# Connections.net
KiCad netlist of a schematic drawn in EAGLE
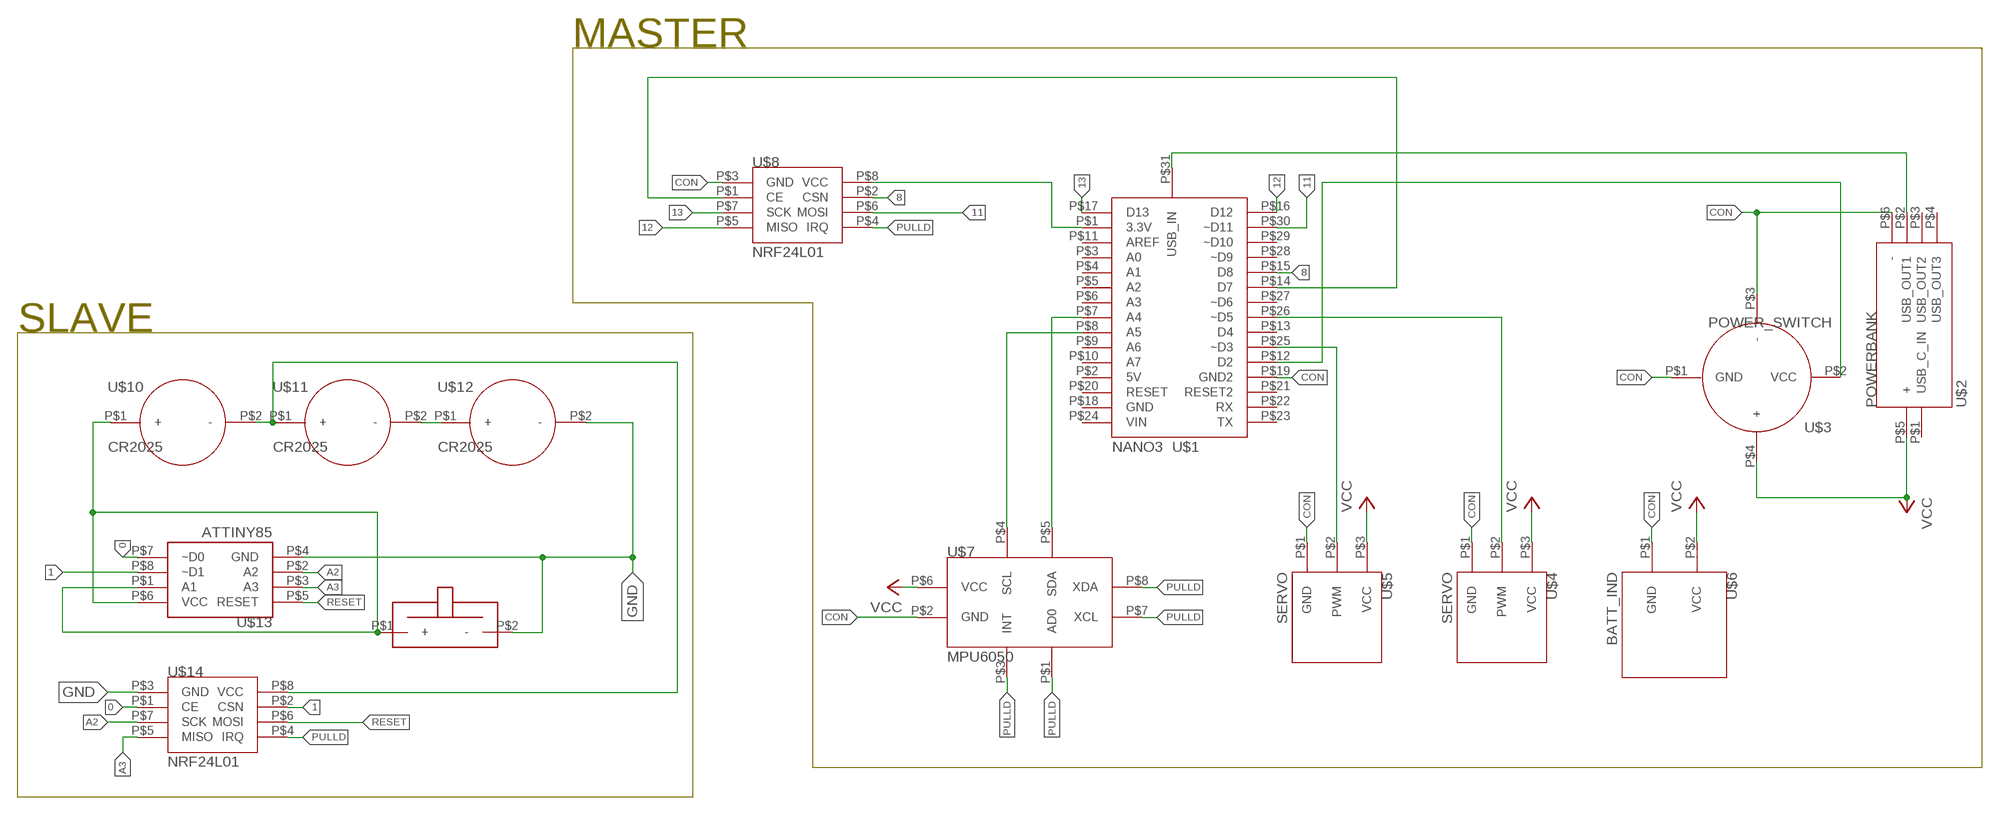
[diagram p0: schematic, sheet 1]

(export (version "E")
  (design (tool "Eeschema 10.0.6"))
  (components
    (comp (ref "U$1")
      (value "NANO3")
      (footprint "eagle-import:NANO3")
      (libsource (lib "eagle-import") (part "NANO3"))
    )
    (comp (ref "U$2")
      (value "POWERBANK")
      (footprint "eagle-import:POWERBANK")
      (libsource (lib "eagle-import") (part "POWERBANK"))
    )
    (comp (ref "U$3")
      (value "POWER_SWITCH")
      (footprint "eagle-import:POWER_SWITCH")
      (libsource (lib "eagle-import") (part "POWER_SWITCH"))
    )
    (comp (ref "U$4")
      (value "SERVO")
      (footprint "eagle-import:SERVO")
      (libsource (lib "eagle-import") (part "SERVO"))
    )
    (comp (ref "U$5")
      (value "SERVO")
      (footprint "eagle-import:SERVO")
      (libsource (lib "eagle-import") (part "SERVO"))
    )
    (comp (ref "U$6")
      (value "BATT_IND")
      (footprint "eagle-import:BATT_IND")
      (libsource (lib "eagle-import") (part "BATT_IND"))
    )
    (comp (ref "U$7")
      (value "MPU6050")
      (footprint "eagle-import:MPU6050")
      (libsource (lib "eagle-import") (part "MPU6050"))
    )
    (comp (ref "U$8")
      (value "NRF24L01")
      (footprint "eagle-import:NRF24L01")
      (libsource (lib "eagle-import") (part "NRF24L01"))
    )
    (comp (ref "U$9")
      (value "SPST")
      (footprint "eagle-import:SPST")
      (libsource (lib "eagle-import") (part "SPST"))
    )
    (comp (ref "U$10")
      (value "CR2025")
      (footprint "eagle-import:CR2025")
      (libsource (lib "eagle-import") (part "CR2025"))
    )
    (comp (ref "U$11")
      (value "CR2025")
      (footprint "eagle-import:CR2025")
      (libsource (lib "eagle-import") (part "CR2025"))
    )
    (comp (ref "U$12")
      (value "CR2025")
      (footprint "eagle-import:CR2025")
      (libsource (lib "eagle-import") (part "CR2025"))
    )
    (comp (ref "U$13")
      (value "ATTINY85")
      (footprint "eagle-import:ATTINY85")
      (libsource (lib "eagle-import") (part "ATTINY85"))
    )
    (comp (ref "U$14")
      (value "NRF24L01")
      (footprint "eagle-import:NRF24L01")
      (libsource (lib "eagle-import") (part "NRF24L01"))
    )
  )
  (nets
    (net (code "1") (name "0") (class "Default")
      (node (ref "U$13") (pin "P$7") (pinfunction "~{D0}_P$7") (pintype "bidirectional"))
    )
    (net (code "2") (name "1") (class "Default")
      (node (ref "U$13") (pin "P$8") (pinfunction "~{D1}_P$8") (pintype "bidirectional"))
    )
    (net (code "3") (name "8") (class "Default")
      (node (ref "U$1") (pin "P$15") (pinfunction "D8_P$15") (pintype "bidirectional"))
    )
    (net (code "4") (name "11") (class "Default")
      (node (ref "U$1") (pin "P$30") (pinfunction "~{D11}_P$30") (pintype "bidirectional"))
    )
    (net (code "5") (name "12") (class "Default")
      (node (ref "U$8") (pin "P$5") (pinfunction "MISO_P$5") (pintype "bidirectional"))
    )
    (net (code "6") (name "13") (class "Default")
      (node (ref "U$8") (pin "P$7") (pinfunction "SCK_P$7") (pintype "bidirectional"))
    )
    (net (code "7") (name "A2") (class "Default")
      (node (ref "U$13") (pin "P$2") (pinfunction "A2_P$2") (pintype "bidirectional"))
    )
    (net (code "8") (name "A3") (class "Default")
      (node (ref "U$13") (pin "P$3") (pinfunction "A3_P$3") (pintype "bidirectional"))
    )
    (net (code "9") (name "CON") (class "Default")
      (node (ref "U$1") (pin "P$19") (pinfunction "GND2_P$19") (pintype "bidirectional"))
    )
    (net (code "10") (name "GND") (class "Default")
      (node (ref "U$12") (pin "P$2") (pinfunction "-_P$2") (pintype "bidirectional"))
      (node (ref "U$13") (pin "P$4") (pinfunction "GND_P$4") (pintype "bidirectional"))
      (node (ref "U$9") (pin "P$2") (pinfunction "-_P$2") (pintype "bidirectional"))
    )
    (net (code "11") (name "Net-(U$1-3.3V)") (class "Default")
      (node (ref "U$1") (pin "P$1") (pinfunction "3.3V_P$1") (pintype "bidirectional"))
      (node (ref "U$8") (pin "P$8") (pinfunction "VCC_P$8") (pintype "bidirectional"))
    )
    (net (code "12") (name "Net-(U$1-A4)") (class "Default")
      (node (ref "U$1") (pin "P$7") (pinfunction "A4_P$7") (pintype "bidirectional"))
      (node (ref "U$7") (pin "P$5") (pinfunction "SDA_P$5") (pintype "bidirectional"))
    )
    (net (code "13") (name "Net-(U$1-A5)") (class "Default")
      (node (ref "U$1") (pin "P$8") (pinfunction "A5_P$8") (pintype "bidirectional"))
      (node (ref "U$7") (pin "P$4") (pinfunction "SCL_P$4") (pintype "bidirectional"))
    )
    (net (code "14") (name "Net-(U$1-D2)") (class "Default")
      (node (ref "U$1") (pin "P$12") (pinfunction "D2_P$12") (pintype "bidirectional"))
      (node (ref "U$3") (pin "P$2") (pinfunction "VCC_P$2") (pintype "bidirectional"))
    )
    (net (code "15") (name "Net-(U$1-D7)") (class "Default")
      (node (ref "U$1") (pin "P$14") (pinfunction "D7_P$14") (pintype "bidirectional"))
      (node (ref "U$8") (pin "P$1") (pinfunction "CE_P$1") (pintype "bidirectional"))
    )
    (net (code "16") (name "Net-(U$1-USB_IN)") (class "Default")
      (node (ref "U$1") (pin "P$31") (pinfunction "USB_IN_P$31") (pintype "bidirectional"))
      (node (ref "U$2") (pin "P$2") (pinfunction "USB_OUT1_P$2") (pintype "bidirectional"))
    )
    (net (code "17") (name "Net-(U$1-~{D3})") (class "Default")
      (node (ref "U$1") (pin "P$25") (pinfunction "~{D3}_P$25") (pintype "bidirectional"))
      (node (ref "U$5") (pin "P$2") (pinfunction "PWM_P$2") (pintype "bidirectional"))
    )
    (net (code "18") (name "Net-(U$1-~{D5})") (class "Default")
      (node (ref "U$1") (pin "P$26") (pinfunction "~{D5}_P$26") (pintype "bidirectional"))
      (node (ref "U$4") (pin "P$2") (pinfunction "PWM_P$2") (pintype "bidirectional"))
    )
    (net (code "19") (name "Net-(U$2--)") (class "Default")
      (node (ref "U$2") (pin "P$6") (pinfunction "-_P$6") (pintype "bidirectional"))
      (node (ref "U$3") (pin "P$3") (pinfunction "-_P$3") (pintype "bidirectional"))
    )
    (net (code "20") (name "Net-(U$10-+)") (class "Default")
      (node (ref "U$10") (pin "P$1") (pinfunction "+_P$1") (pintype "bidirectional"))
      (node (ref "U$13") (pin "P$1") (pinfunction "A1_P$1") (pintype "bidirectional"))
      (node (ref "U$13") (pin "P$6") (pinfunction "VCC_P$6") (pintype "bidirectional"))
      (node (ref "U$9") (pin "P$1") (pinfunction "+_P$1") (pintype "bidirectional"))
    )
    (net (code "21") (name "Net-(U$10--)") (class "Default")
      (node (ref "U$10") (pin "P$2") (pinfunction "-_P$2") (pintype "bidirectional"))
      (node (ref "U$11") (pin "P$1") (pinfunction "+_P$1") (pintype "bidirectional"))
      (node (ref "U$14") (pin "P$8") (pinfunction "VCC_P$8") (pintype "bidirectional"))
    )
    (net (code "22") (name "Net-(U$11--)") (class "Default")
      (node (ref "U$11") (pin "P$2") (pinfunction "-_P$2") (pintype "bidirectional"))
      (node (ref "U$12") (pin "P$1") (pinfunction "+_P$1") (pintype "bidirectional"))
    )
    (net (code "23") (name "PULLD") (class "Default")
      (node (ref "U$7") (pin "P$8") (pinfunction "XDA_P$8") (pintype "bidirectional"))
    )
    (net (code "24") (name "RESET") (class "Default")
      (node (ref "U$13") (pin "P$5") (pinfunction "RESET_P$5") (pintype "bidirectional"))
    )
    (net (code "25") (name "VCC") (class "Default")
      (node (ref "U$2") (pin "P$5") (pinfunction "+_P$5") (pintype "bidirectional"))
      (node (ref "U$3") (pin "P$4") (pinfunction "+_P$4") (pintype "bidirectional"))
      (node (ref "U$4") (pin "P$3") (pinfunction "VCC_P$3") (pintype "bidirectional"))
      (node (ref "U$5") (pin "P$3") (pinfunction "VCC_P$3") (pintype "bidirectional"))
      (node (ref "U$6") (pin "P$2") (pinfunction "VCC_P$2") (pintype "bidirectional"))
      (node (ref "U$7") (pin "P$6") (pinfunction "VCC_P$6") (pintype "bidirectional"))
    )
    (net (code "26") (name "unconnected-(U$1-5V-PadP$2)") (class "Default")
      (node (ref "U$1") (pin "P$2") (pinfunction "5V_P$2") (pintype "bidirectional"))
    )
    (net (code "27") (name "unconnected-(U$1-A0-PadP$3)") (class "Default")
      (node (ref "U$1") (pin "P$3") (pinfunction "A0_P$3") (pintype "bidirectional"))
    )
    (net (code "28") (name "unconnected-(U$1-A1-PadP$4)") (class "Default")
      (node (ref "U$1") (pin "P$4") (pinfunction "A1_P$4") (pintype "bidirectional"))
    )
    (net (code "29") (name "unconnected-(U$1-A2-PadP$5)") (class "Default")
      (node (ref "U$1") (pin "P$5") (pinfunction "A2_P$5") (pintype "bidirectional"))
    )
    (net (code "30") (name "unconnected-(U$1-A3-PadP$6)") (class "Default")
      (node (ref "U$1") (pin "P$6") (pinfunction "A3_P$6") (pintype "bidirectional"))
    )
    (net (code "31") (name "unconnected-(U$1-A6-PadP$9)") (class "Default")
      (node (ref "U$1") (pin "P$9") (pinfunction "A6_P$9") (pintype "bidirectional"))
    )
    (net (code "32") (name "unconnected-(U$1-A7-PadP$10)") (class "Default")
      (node (ref "U$1") (pin "P$10") (pinfunction "A7_P$10") (pintype "bidirectional"))
    )
    (net (code "33") (name "unconnected-(U$1-AREF-PadP$11)") (class "Default")
      (node (ref "U$1") (pin "P$11") (pinfunction "AREF_P$11") (pintype "bidirectional"))
    )
    (net (code "34") (name "unconnected-(U$1-D4-PadP$13)") (class "Default")
      (node (ref "U$1") (pin "P$13") (pinfunction "D4_P$13") (pintype "bidirectional"))
    )
    (net (code "35") (name "unconnected-(U$1-D12-PadP$16)") (class "Default")
      (node (ref "U$1") (pin "P$16") (pinfunction "D12_P$16") (pintype "bidirectional"))
    )
    (net (code "36") (name "unconnected-(U$1-D13-PadP$17)") (class "Default")
      (node (ref "U$1") (pin "P$17") (pinfunction "D13_P$17") (pintype "bidirectional"))
    )
    (net (code "37") (name "unconnected-(U$1-GND-PadP$18)") (class "Default")
      (node (ref "U$1") (pin "P$18") (pinfunction "GND_P$18") (pintype "bidirectional"))
    )
    (net (code "38") (name "unconnected-(U$1-RESET-PadP$20)") (class "Default")
      (node (ref "U$1") (pin "P$20") (pinfunction "RESET_P$20") (pintype "bidirectional"))
    )
    (net (code "39") (name "unconnected-(U$1-RESET2-PadP$21)") (class "Default")
      (node (ref "U$1") (pin "P$21") (pinfunction "RESET2_P$21") (pintype "bidirectional"))
    )
    (net (code "40") (name "unconnected-(U$1-RX-PadP$22)") (class "Default")
      (node (ref "U$1") (pin "P$22") (pinfunction "RX_P$22") (pintype "bidirectional"))
    )
    (net (code "41") (name "unconnected-(U$1-TX-PadP$23)") (class "Default")
      (node (ref "U$1") (pin "P$23") (pinfunction "TX_P$23") (pintype "bidirectional"))
    )
    (net (code "42") (name "unconnected-(U$1-VIN-PadP$24)") (class "Default")
      (node (ref "U$1") (pin "P$24") (pinfunction "VIN_P$24") (pintype "bidirectional"))
    )
    (net (code "43") (name "unconnected-(U$1-~{D6}-PadP$27)") (class "Default")
      (node (ref "U$1") (pin "P$27") (pinfunction "~{D6}_P$27") (pintype "bidirectional"))
    )
    (net (code "44") (name "unconnected-(U$1-~{D9}-PadP$28)") (class "Default")
      (node (ref "U$1") (pin "P$28") (pinfunction "~{D9}_P$28") (pintype "bidirectional"))
    )
    (net (code "45") (name "unconnected-(U$1-~{D10}-PadP$29)") (class "Default")
      (node (ref "U$1") (pin "P$29") (pinfunction "~{D10}_P$29") (pintype "bidirectional"))
    )
    (net (code "46") (name "unconnected-(U$2-USB_C_IN-PadP$1)") (class "Default")
      (node (ref "U$2") (pin "P$1") (pinfunction "USB_C_IN_P$1") (pintype "bidirectional"))
    )
    (net (code "47") (name "unconnected-(U$2-USB_OUT2-PadP$3)") (class "Default")
      (node (ref "U$2") (pin "P$3") (pinfunction "USB_OUT2_P$3") (pintype "bidirectional"))
    )
    (net (code "48") (name "unconnected-(U$2-USB_OUT3-PadP$4)") (class "Default")
      (node (ref "U$2") (pin "P$4") (pinfunction "USB_OUT3_P$4") (pintype "bidirectional"))
    )
    (net (code "49") (name "unconnected-(U$3-GND-PadP$1)") (class "Default")
      (node (ref "U$3") (pin "P$1") (pinfunction "GND_P$1") (pintype "bidirectional"))
    )
    (net (code "50") (name "unconnected-(U$4-GND-PadP$1)") (class "Default")
      (node (ref "U$4") (pin "P$1") (pinfunction "GND_P$1") (pintype "bidirectional"))
    )
    (net (code "51") (name "unconnected-(U$5-GND-PadP$1)") (class "Default")
      (node (ref "U$5") (pin "P$1") (pinfunction "GND_P$1") (pintype "bidirectional"))
    )
    (net (code "52") (name "unconnected-(U$6-GND-PadP$1)") (class "Default")
      (node (ref "U$6") (pin "P$1") (pinfunction "GND_P$1") (pintype "bidirectional"))
    )
    (net (code "53") (name "unconnected-(U$7-AD0-PadP$1)") (class "Default")
      (node (ref "U$7") (pin "P$1") (pinfunction "AD0_P$1") (pintype "bidirectional"))
    )
    (net (code "54") (name "unconnected-(U$7-GND-PadP$2)") (class "Default")
      (node (ref "U$7") (pin "P$2") (pinfunction "GND_P$2") (pintype "bidirectional"))
    )
    (net (code "55") (name "unconnected-(U$7-INT-PadP$3)") (class "Default")
      (node (ref "U$7") (pin "P$3") (pinfunction "INT_P$3") (pintype "bidirectional"))
    )
    (net (code "56") (name "unconnected-(U$7-XCL-PadP$7)") (class "Default")
      (node (ref "U$7") (pin "P$7") (pinfunction "XCL_P$7") (pintype "bidirectional"))
    )
    (net (code "57") (name "unconnected-(U$8-CSN-PadP$2)") (class "Default")
      (node (ref "U$8") (pin "P$2") (pinfunction "CSN_P$2") (pintype "bidirectional"))
    )
    (net (code "58") (name "unconnected-(U$8-GND-PadP$3)") (class "Default")
      (node (ref "U$8") (pin "P$3") (pinfunction "GND_P$3") (pintype "bidirectional"))
    )
    (net (code "59") (name "unconnected-(U$8-IRQ-PadP$4)") (class "Default")
      (node (ref "U$8") (pin "P$4") (pinfunction "IRQ_P$4") (pintype "bidirectional"))
    )
    (net (code "60") (name "unconnected-(U$8-MOSI-PadP$6)") (class "Default")
      (node (ref "U$8") (pin "P$6") (pinfunction "MOSI_P$6") (pintype "bidirectional"))
    )
    (net (code "61") (name "unconnected-(U$14-CE-PadP$1)") (class "Default")
      (node (ref "U$14") (pin "P$1") (pinfunction "CE_P$1") (pintype "bidirectional"))
    )
    (net (code "62") (name "unconnected-(U$14-CSN-PadP$2)") (class "Default")
      (node (ref "U$14") (pin "P$2") (pinfunction "CSN_P$2") (pintype "bidirectional"))
    )
    (net (code "63") (name "unconnected-(U$14-GND-PadP$3)") (class "Default")
      (node (ref "U$14") (pin "P$3") (pinfunction "GND_P$3") (pintype "bidirectional"))
    )
    (net (code "64") (name "unconnected-(U$14-IRQ-PadP$4)") (class "Default")
      (node (ref "U$14") (pin "P$4") (pinfunction "IRQ_P$4") (pintype "bidirectional"))
    )
    (net (code "65") (name "unconnected-(U$14-MISO-PadP$5)") (class "Default")
      (node (ref "U$14") (pin "P$5") (pinfunction "MISO_P$5") (pintype "bidirectional"))
    )
    (net (code "66") (name "unconnected-(U$14-MOSI-PadP$6)") (class "Default")
      (node (ref "U$14") (pin "P$6") (pinfunction "MOSI_P$6") (pintype "bidirectional"))
    )
    (net (code "67") (name "unconnected-(U$14-SCK-PadP$7)") (class "Default")
      (node (ref "U$14") (pin "P$7") (pinfunction "SCK_P$7") (pintype "bidirectional"))
    )
  )
)
